# RelojAzul.net
KiCad netlist of a schematic drawn in EAGLE
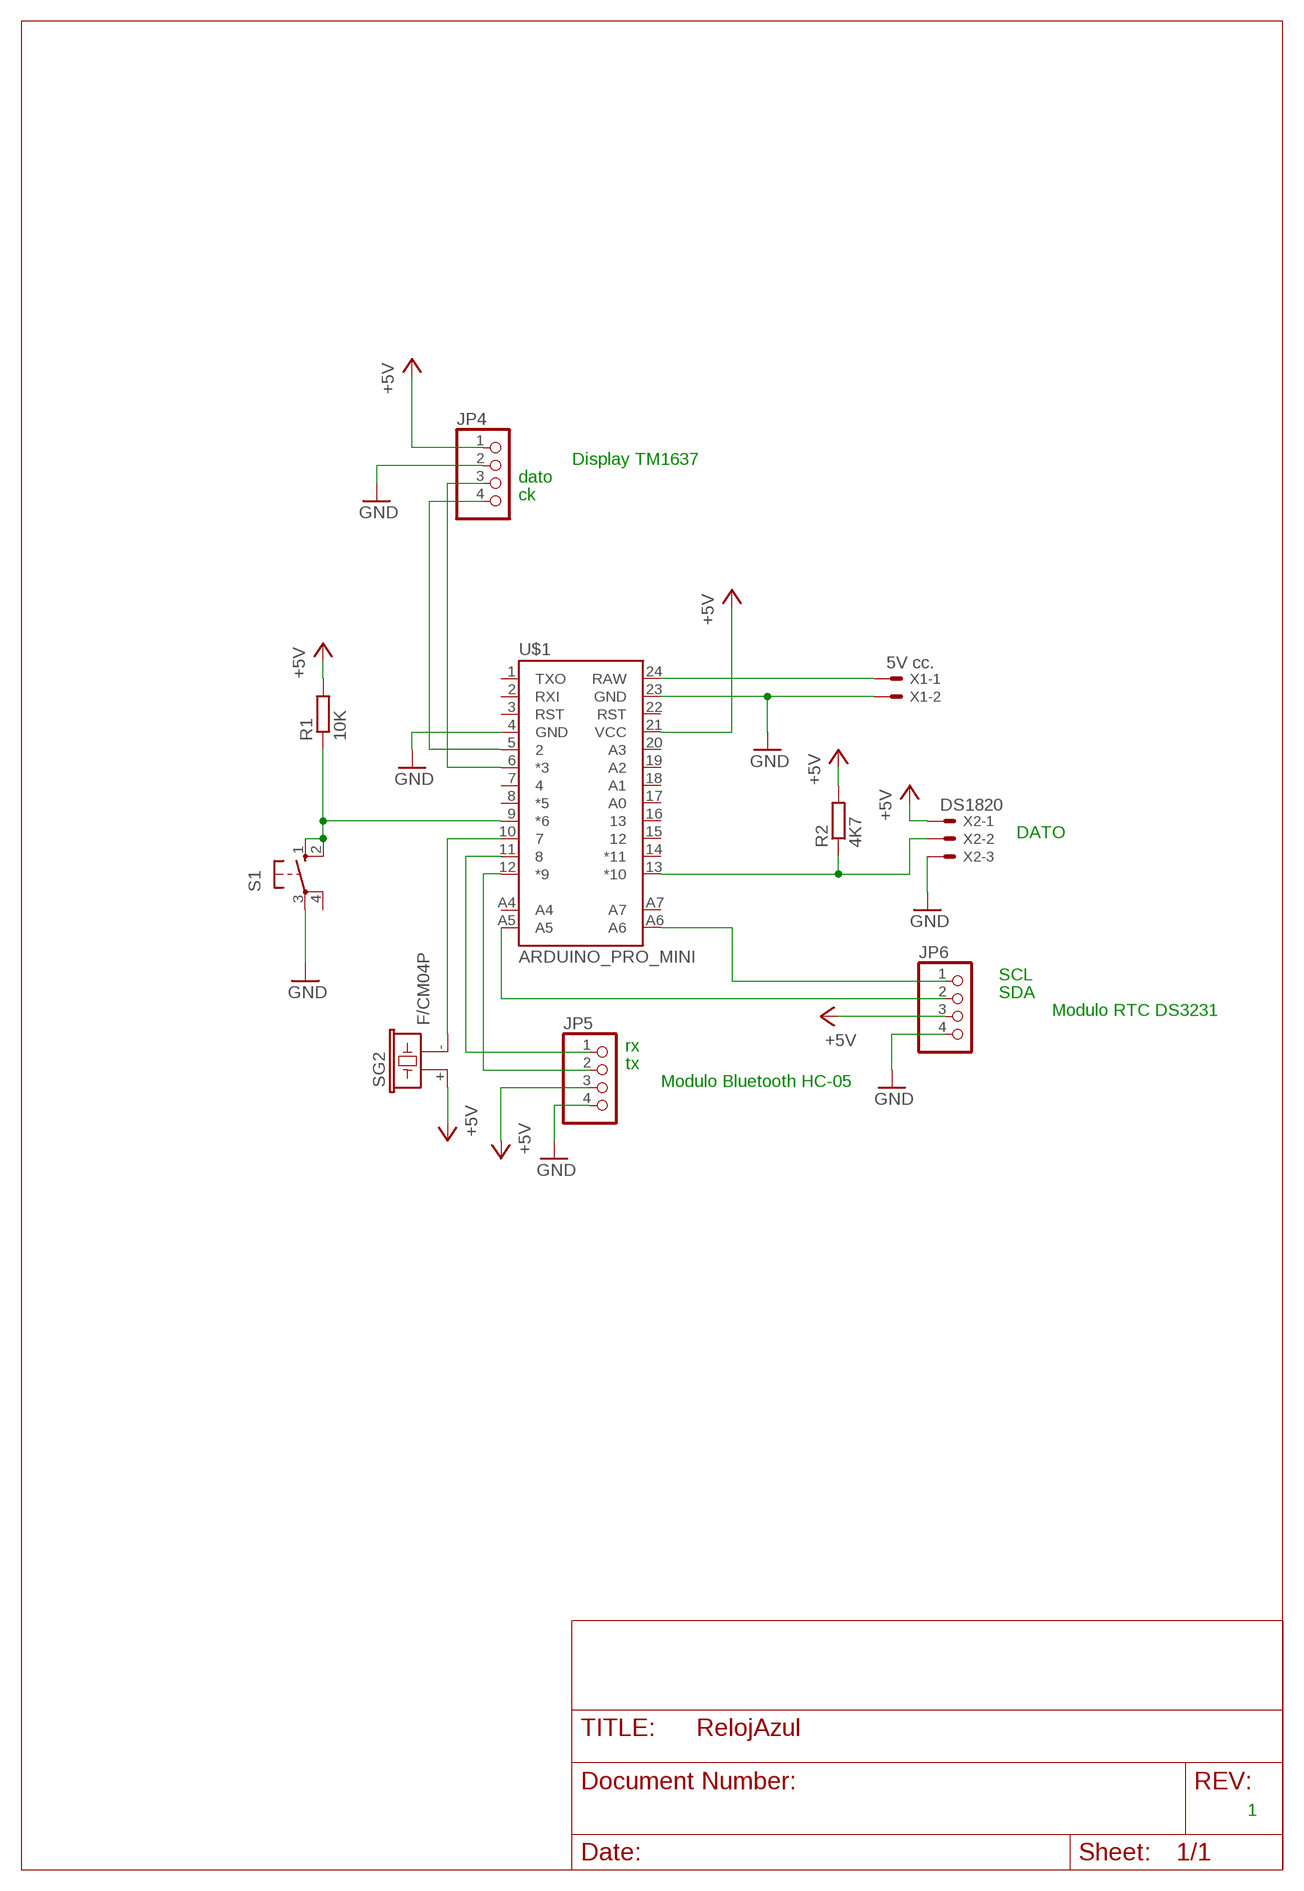
[diagram p0: schematic, sheet 1]

(export (version "E")
  (design (tool "Eeschema 10.0.6"))
  (components
    (comp (ref "JP4")
      (value "PINHD-1X4")
      (footprint "eagle-import:1X04")
      (libsource (lib "eagle-import") (part "PINHD-1X4"))
    )
    (comp (ref "JP5")
      (value "PINHD-1X4")
      (footprint "eagle-import:1X04")
      (libsource (lib "eagle-import") (part "PINHD-1X4"))
    )
    (comp (ref "JP6")
      (value "PINHD-1X4")
      (footprint "eagle-import:1X04")
      (libsource (lib "eagle-import") (part "PINHD-1X4"))
    )
    (comp (ref "R1")
      (value "10K")
      (footprint "eagle-import:0204_5")
      (libsource (lib "eagle-import") (part "R-EU_0204_5"))
    )
    (comp (ref "R2")
      (value "4K7")
      (footprint "eagle-import:0204_5")
      (libsource (lib "eagle-import") (part "R-EU_0204_5"))
    )
    (comp (ref "S1")
      (value "40-XX")
      (footprint "eagle-import:B3F-40XX")
      (fields (field (name "MF") "OMRON COMPONENTS USA") (field (name "MPN") "B3F-4000"))
      (libsource (lib "eagle-import") (part "40-XX"))
    )
    (comp (ref "SG2")
      (value "F/CM04P")
      (footprint "eagle-import:F_CM04P")
      (libsource (lib "eagle-import") (part "F/CM04P"))
    )
    (comp (ref "U$1")
      (value "ARDUINO_PRO_MINI")
      (footprint "eagle-import:ARDUINO_PRO_MINI")
      (libsource (lib "eagle-import") (part "ARDUINO_PRO_MINI"))
    )
    (comp (ref "X1")
      (value "5V cc.")
      (footprint "eagle-import:22-23-2021")
      (fields (field (name "MF") "MOLEX") (field (name "MPN") "22-23-2021"))
      (libsource (lib "eagle-import") (part "22-23-2021"))
    )
    (comp (ref "X2")
      (value "DS1820")
      (footprint "eagle-import:22-23-2031")
      (fields (field (name "MF") "MOLEX") (field (name "MPN") "22-23-2031"))
      (libsource (lib "eagle-import") (part "22-23-2031"))
    )
  )
  (nets
    (net (code "1") (name "+5V") (class "Default")
      (node (ref "JP4") (pin "1") (pinfunction "1_1") (pintype "passive"))
      (node (ref "JP5") (pin "3") (pinfunction "3_3") (pintype "passive"))
      (node (ref "JP6") (pin "3") (pinfunction "3_3") (pintype "passive"))
      (node (ref "R1") (pin "2") (pinfunction "2_2") (pintype "passive"))
      (node (ref "R2") (pin "2") (pinfunction "2_2") (pintype "passive"))
      (node (ref "SG2") (pin "+") (pinfunction "1_+") (pintype "passive"))
      (node (ref "U$1") (pin "21") (pinfunction "VCC_21") (pintype "bidirectional"))
      (node (ref "X2") (pin "1") (pinfunction "S_1") (pintype "passive"))
    )
    (net (code "2") (name "GND") (class "Default")
      (node (ref "JP4") (pin "2") (pinfunction "2_2") (pintype "passive"))
      (node (ref "JP5") (pin "4") (pinfunction "4_4") (pintype "passive"))
      (node (ref "JP6") (pin "4") (pinfunction "4_4") (pintype "passive"))
      (node (ref "S1") (pin "3") (pinfunction "P_3") (pintype "passive"))
      (node (ref "U$1") (pin "23") (pinfunction "GND_23") (pintype "bidirectional"))
      (node (ref "U$1") (pin "4") (pinfunction "GND_4") (pintype "bidirectional"))
      (node (ref "X1") (pin "2") (pinfunction "S_2") (pintype "passive"))
      (node (ref "X2") (pin "3") (pinfunction "S_3") (pintype "passive"))
    )
    (net (code "3") (name "Net-(JP6-Pad1)") (class "Default")
      (node (ref "JP6") (pin "1") (pinfunction "1_1") (pintype "passive"))
      (node (ref "U$1") (pin "A6") (pinfunction "A6_A6") (pintype "bidirectional"))
    )
    (net (code "4") (name "Net-(JP6-Pad2)") (class "Default")
      (node (ref "JP6") (pin "2") (pinfunction "2_2") (pintype "passive"))
      (node (ref "U$1") (pin "A5") (pinfunction "A5_A5") (pintype "bidirectional"))
    )
    (net (code "5") (name "Net-(S1-S)") (class "Default")
      (node (ref "R1") (pin "1") (pinfunction "1_1") (pintype "passive"))
      (node (ref "S1") (pin "1") (pinfunction "S_1") (pintype "passive"))
      (node (ref "S1") (pin "2") (pinfunction "S1_2") (pintype "passive"))
      (node (ref "U$1") (pin "9") (pinfunction "*6_9") (pintype "bidirectional"))
    )
    (net (code "6") (name "Net-(SG2-2)") (class "Default")
      (node (ref "SG2") (pin "-") (pinfunction "2_-") (pintype "passive"))
      (node (ref "U$1") (pin "10") (pinfunction "7_10") (pintype "bidirectional"))
    )
    (net (code "7") (name "Net-(U$1-*3)") (class "Default")
      (node (ref "JP4") (pin "3") (pinfunction "3_3") (pintype "passive"))
      (node (ref "U$1") (pin "6") (pinfunction "*3_6") (pintype "bidirectional"))
    )
    (net (code "8") (name "Net-(U$1-*9)") (class "Default")
      (node (ref "JP5") (pin "2") (pinfunction "2_2") (pintype "passive"))
      (node (ref "U$1") (pin "12") (pinfunction "*9_12") (pintype "bidirectional"))
    )
    (net (code "9") (name "Net-(U$1-*10)") (class "Default")
      (node (ref "R2") (pin "1") (pinfunction "1_1") (pintype "passive"))
      (node (ref "U$1") (pin "13") (pinfunction "*10_13") (pintype "bidirectional"))
      (node (ref "X2") (pin "2") (pinfunction "S_2") (pintype "passive"))
    )
    (net (code "10") (name "Net-(U$1-2)") (class "Default")
      (node (ref "JP4") (pin "4") (pinfunction "4_4") (pintype "passive"))
      (node (ref "U$1") (pin "5") (pinfunction "2_5") (pintype "bidirectional"))
    )
    (net (code "11") (name "Net-(U$1-8)") (class "Default")
      (node (ref "JP5") (pin "1") (pinfunction "1_1") (pintype "passive"))
      (node (ref "U$1") (pin "11") (pinfunction "8_11") (pintype "bidirectional"))
    )
    (net (code "12") (name "Net-(U$1-RAW)") (class "Default")
      (node (ref "U$1") (pin "24") (pinfunction "RAW_24") (pintype "bidirectional"))
      (node (ref "X1") (pin "1") (pinfunction "S_1") (pintype "passive"))
    )
    (net (code "13") (name "unconnected-(S1-P1-Pad4)") (class "Default")
      (node (ref "S1") (pin "4") (pinfunction "P1_4") (pintype "passive"))
    )
    (net (code "14") (name "unconnected-(U$1-*5-Pad8)") (class "Default")
      (node (ref "U$1") (pin "8") (pinfunction "*5_8") (pintype "bidirectional"))
    )
    (net (code "15") (name "unconnected-(U$1-*11-Pad14)") (class "Default")
      (node (ref "U$1") (pin "14") (pinfunction "*11_14") (pintype "bidirectional"))
    )
    (net (code "16") (name "unconnected-(U$1-4-Pad7)") (class "Default")
      (node (ref "U$1") (pin "7") (pinfunction "4_7") (pintype "bidirectional"))
    )
    (net (code "17") (name "unconnected-(U$1-12-Pad15)") (class "Default")
      (node (ref "U$1") (pin "15") (pinfunction "12_15") (pintype "bidirectional"))
    )
    (net (code "18") (name "unconnected-(U$1-13-Pad16)") (class "Default")
      (node (ref "U$1") (pin "16") (pinfunction "13_16") (pintype "bidirectional"))
    )
    (net (code "19") (name "unconnected-(U$1-A0-Pad17)") (class "Default")
      (node (ref "U$1") (pin "17") (pinfunction "A0_17") (pintype "bidirectional"))
    )
    (net (code "20") (name "unconnected-(U$1-A1-Pad18)") (class "Default")
      (node (ref "U$1") (pin "18") (pinfunction "A1_18") (pintype "bidirectional"))
    )
    (net (code "21") (name "unconnected-(U$1-A2-Pad19)") (class "Default")
      (node (ref "U$1") (pin "19") (pinfunction "A2_19") (pintype "bidirectional"))
    )
    (net (code "22") (name "unconnected-(U$1-A3-Pad20)") (class "Default")
      (node (ref "U$1") (pin "20") (pinfunction "A3_20") (pintype "bidirectional"))
    )
    (net (code "23") (name "unconnected-(U$1-PadA4)") (class "Default")
      (node (ref "U$1") (pin "A4") (pinfunction "A4_A4") (pintype "bidirectional"))
    )
    (net (code "24") (name "unconnected-(U$1-PadA7)") (class "Default")
      (node (ref "U$1") (pin "A7") (pinfunction "A7_A7") (pintype "bidirectional"))
    )
    (net (code "25") (name "unconnected-(U$1-RST-Pad3)") (class "Default")
      (node (ref "U$1") (pin "3") (pinfunction "RST_3") (pintype "bidirectional"))
    )
    (net (code "26") (name "unconnected-(U$1-RST-Pad22)") (class "Default")
      (node (ref "U$1") (pin "22") (pinfunction "RST_22") (pintype "bidirectional"))
    )
    (net (code "27") (name "unconnected-(U$1-RXI-Pad2)") (class "Default")
      (node (ref "U$1") (pin "2") (pinfunction "RXI_2") (pintype "bidirectional"))
    )
    (net (code "28") (name "unconnected-(U$1-TXO-Pad1)") (class "Default")
      (node (ref "U$1") (pin "1") (pinfunction "TXO_1") (pintype "bidirectional"))
    )
  )
)
